# TSOC_GROVEY_WIFI_R0_1.net
KiCad netlist of a schematic drawn in EAGLE
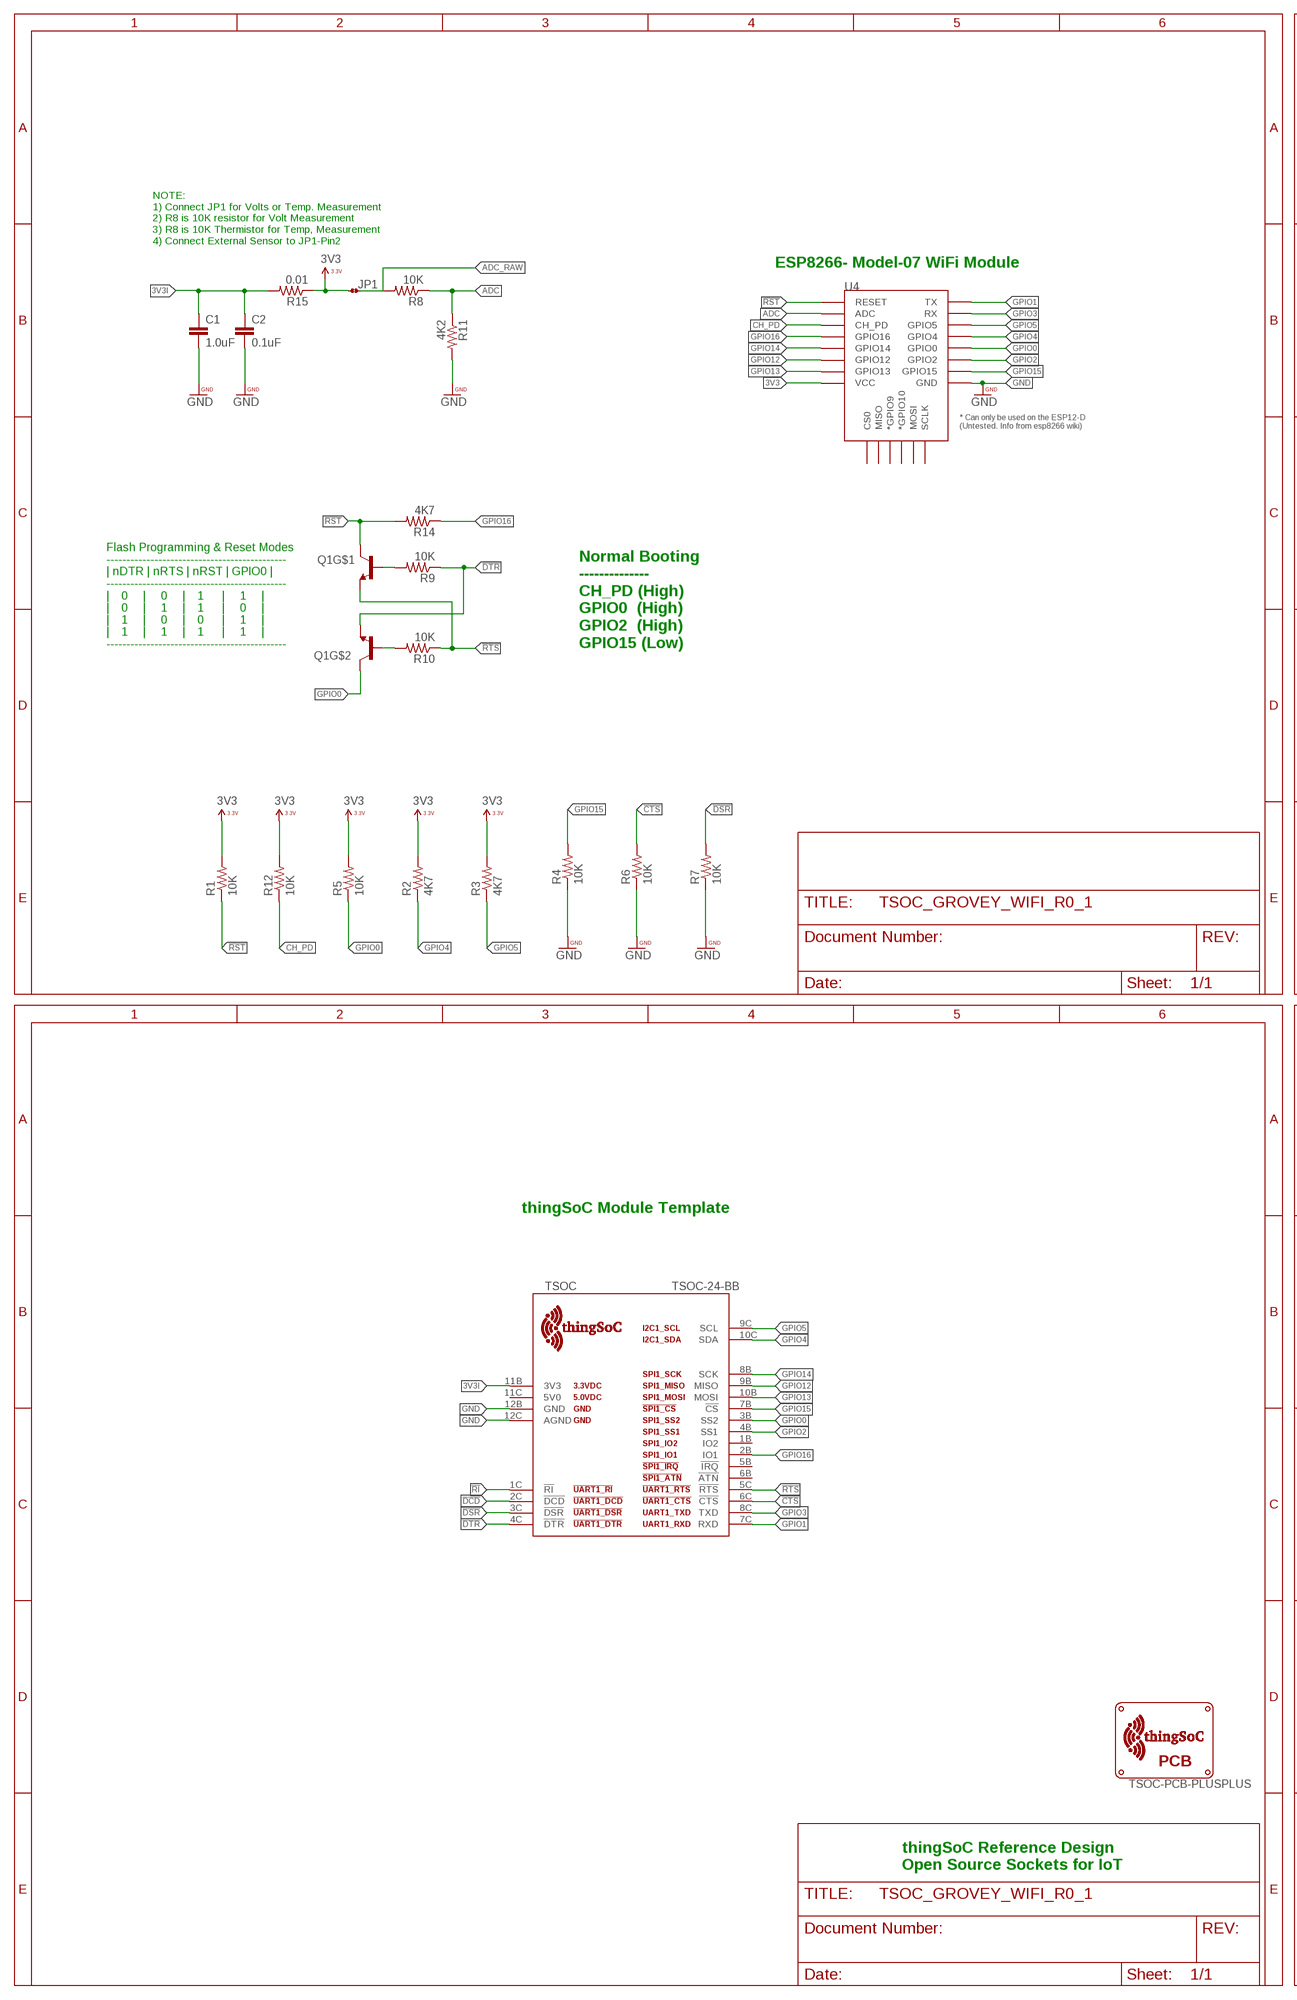
[diagram p0: schematic, sheet 1, part 1 of 2]
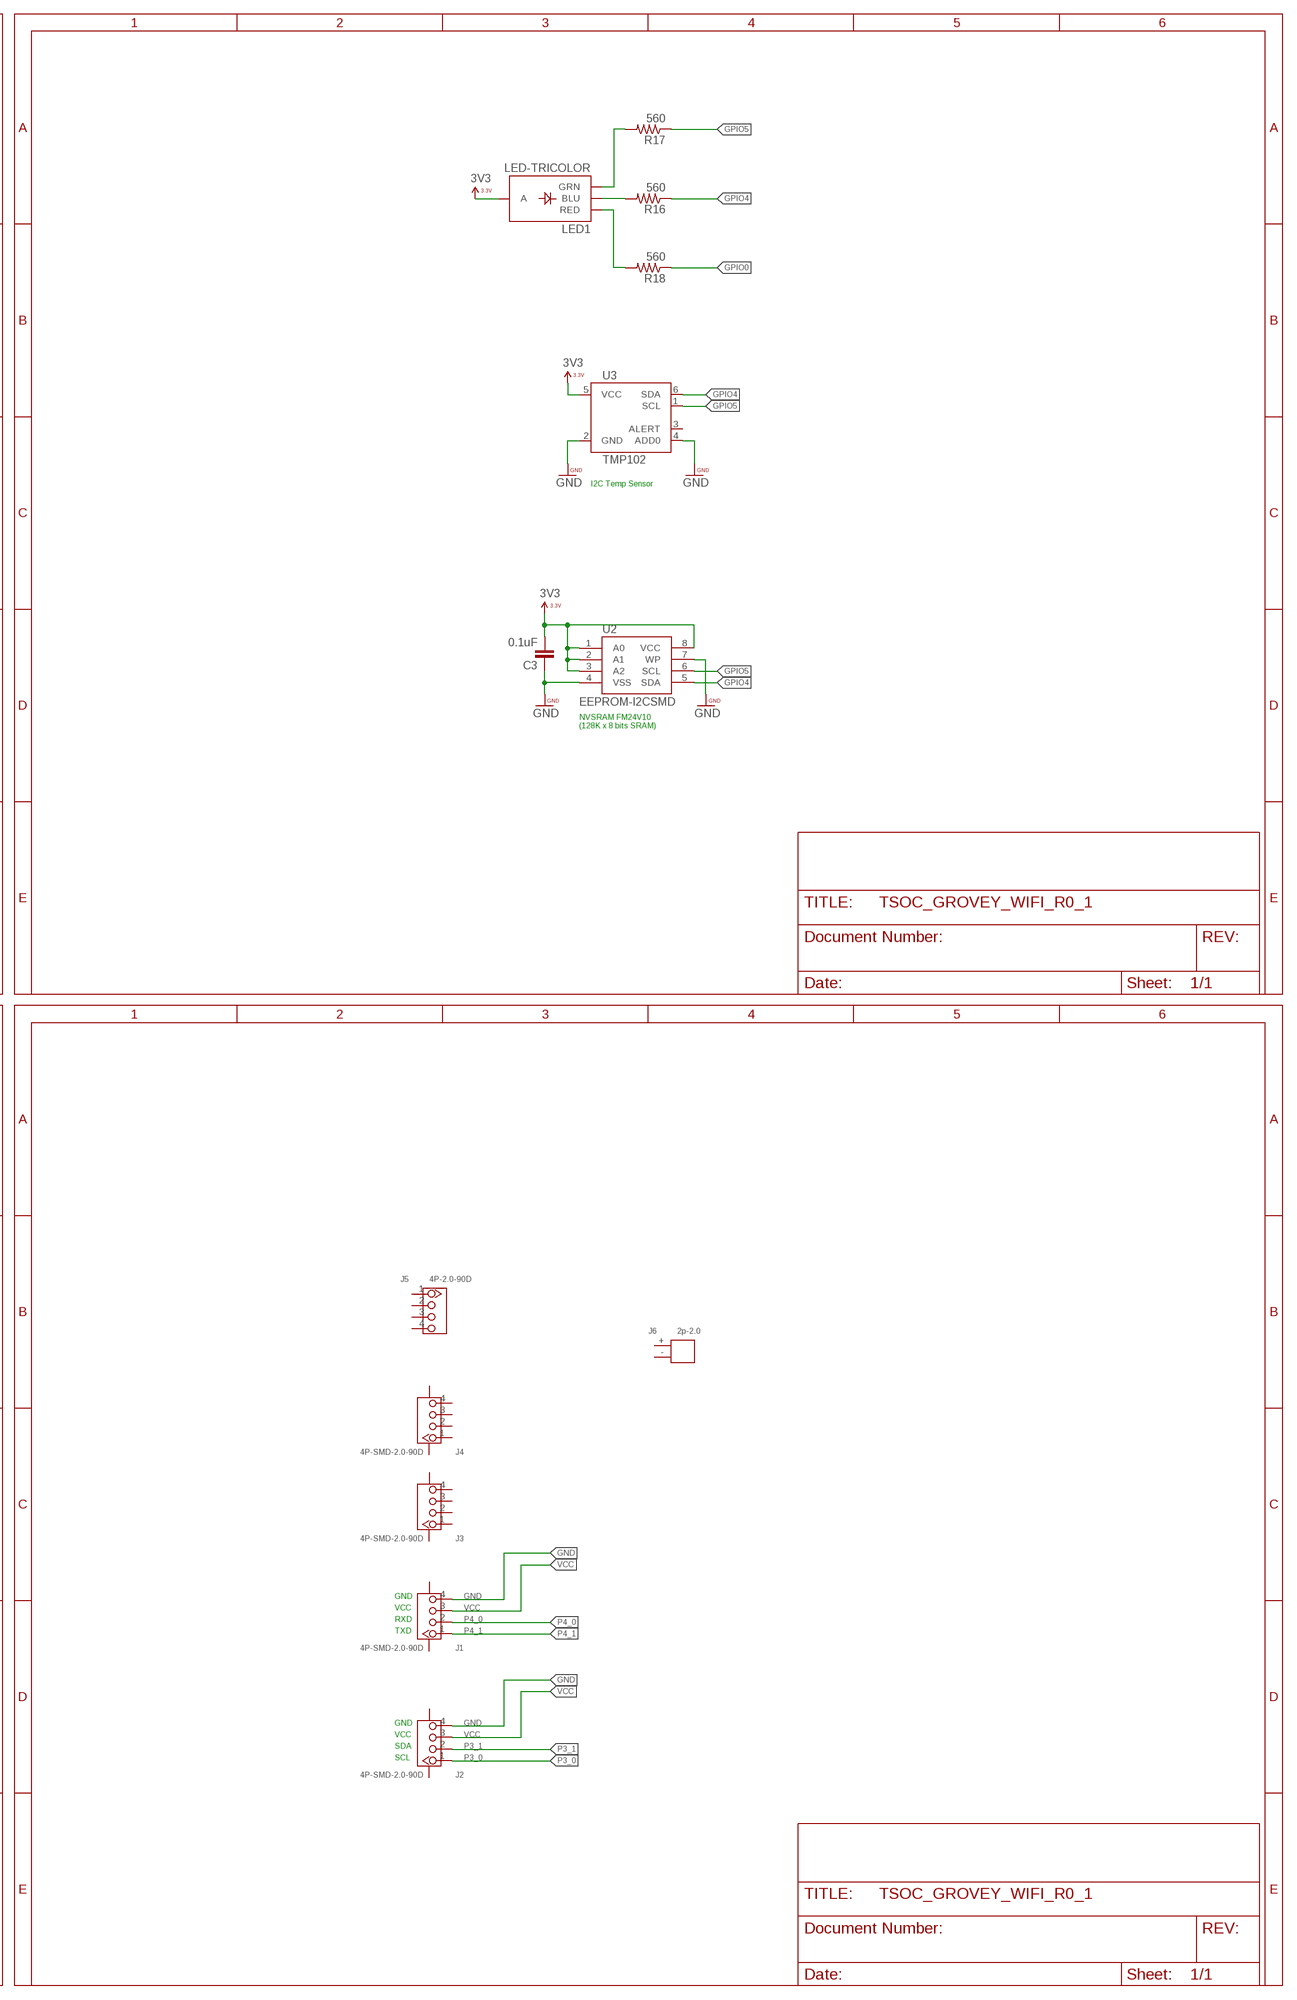
[diagram p1: schematic, sheet 1, part 2 of 2]

(export (version "E")
  (design (tool "Eeschema 10.0.6"))
  (components
    (comp (ref "C1")
      (value "1.0uF")
      (footprint "eagle-import:0402-CAP")
      (libsource (lib "eagle-import") (part "CAP0402-CAP"))
    )
    (comp (ref "C2")
      (value "0.1uF")
      (footprint "eagle-import:0402-CAP")
      (libsource (lib "eagle-import") (part "CAP0402-CAP"))
    )
    (comp (ref "C3")
      (value "0.1uF")
      (footprint "eagle-import:0402-CAP")
      (libsource (lib "eagle-import") (part "CAP0402-CAP"))
    )
    (comp (ref "J1")
      (value "4P-SMD-2.0-90D")
      (footprint "eagle-import:HW4-SMD-2.0-90D")
      (libsource (lib "eagle-import") (part "GROVE-CONNECTOR-SMD-90D(4+2P-2.0)"))
    )
    (comp (ref "J2")
      (value "4P-SMD-2.0-90D")
      (footprint "eagle-import:HW4-SMD-2.0-90D")
      (libsource (lib "eagle-import") (part "GROVE-CONNECTOR-SMD-90D(4+2P-2.0)"))
    )
    (comp (ref "J3")
      (value "4P-SMD-2.0-90D")
      (footprint "eagle-import:HW4-SMD-2.0-90D")
      (libsource (lib "eagle-import") (part "GROVE-CONNECTOR-SMD-90D(4+2P-2.0)"))
    )
    (comp (ref "J4")
      (value "4P-SMD-2.0-90D")
      (footprint "eagle-import:HW4-SMD-2.0-90D")
      (libsource (lib "eagle-import") (part "GROVE-CONNECTOR-SMD-90D(4+2P-2.0)"))
    )
    (comp (ref "J5")
      (value "4P-2.0-90D")
      (footprint "eagle-import:HW4-2.0-90D")
      (libsource (lib "eagle-import") (part "GROVE-CONNECTOR-DIP-90D(4P-2.0)"))
    )
    (comp (ref "J6")
      (value "2p-2.0")
      (footprint "eagle-import:H2-2.0-6X4.5MM")
      (libsource (lib "eagle-import") (part "DIP-JST-2P-2.0"))
    )
    (comp (ref "JP1")
      (value "JMP-2-NO-0402")
      (footprint "eagle-import:JMP-2-NO-0402")
      (libsource (lib "eagle-import") (part "JMP-2-NO-0402"))
    )
    (comp (ref "LED1")
      (value "LED-TRICOLOR")
      (footprint "eagle-import:LED-TRICOLOR-SMD")
      (libsource (lib "eagle-import") (part "LED-TRICOLOR"))
    )
    (comp (ref "Q1")
      (value "MMBT2222A")
      (footprint "eagle-import:SOT363")
      (libsource (lib "eagle-import") (part "MMDT3904"))
    )
    (comp (ref "R1")
      (value "10K")
      (footprint "eagle-import:0402-RES")
      (libsource (lib "eagle-import") (part "RESISTOR0402"))
    )
    (comp (ref "R2")
      (value "4K7")
      (footprint "eagle-import:0402-RES")
      (libsource (lib "eagle-import") (part "RESISTOR0402"))
    )
    (comp (ref "R3")
      (value "4K7")
      (footprint "eagle-import:0402-RES")
      (libsource (lib "eagle-import") (part "RESISTOR0402"))
    )
    (comp (ref "R4")
      (value "10K")
      (footprint "eagle-import:0402-RES")
      (libsource (lib "eagle-import") (part "RESISTOR0402"))
    )
    (comp (ref "R5")
      (value "10K")
      (footprint "eagle-import:0402-RES")
      (libsource (lib "eagle-import") (part "RESISTOR0402"))
    )
    (comp (ref "R6")
      (value "10K")
      (footprint "eagle-import:0402-RES")
      (libsource (lib "eagle-import") (part "RESISTOR0402"))
    )
    (comp (ref "R7")
      (value "10K")
      (footprint "eagle-import:0402-RES")
      (libsource (lib "eagle-import") (part "RESISTOR0402"))
    )
    (comp (ref "R8")
      (value "10K")
      (footprint "eagle-import:0402-RES")
      (libsource (lib "eagle-import") (part "RESISTOR0402"))
    )
    (comp (ref "R9")
      (value "10K")
      (footprint "eagle-import:0402-RES")
      (libsource (lib "eagle-import") (part "RESISTOR0402"))
    )
    (comp (ref "R10")
      (value "10K")
      (footprint "eagle-import:0402-RES")
      (libsource (lib "eagle-import") (part "RESISTOR0402"))
    )
    (comp (ref "R11")
      (value "4K2")
      (footprint "eagle-import:0402-RES")
      (libsource (lib "eagle-import") (part "RESISTOR0402"))
    )
    (comp (ref "R12")
      (value "10K")
      (footprint "eagle-import:0402-RES")
      (libsource (lib "eagle-import") (part "RESISTOR0402"))
    )
    (comp (ref "R14")
      (value "4K7")
      (footprint "eagle-import:0402-RES")
      (libsource (lib "eagle-import") (part "RESISTOR0402"))
    )
    (comp (ref "R15")
      (value "0.01")
      (footprint "eagle-import:0402-RES")
      (libsource (lib "eagle-import") (part "RESISTOR0402"))
    )
    (comp (ref "R16")
      (value "560")
      (footprint "eagle-import:0402-RES")
      (libsource (lib "eagle-import") (part "RESISTOR0402"))
    )
    (comp (ref "R17")
      (value "560")
      (footprint "eagle-import:0402-RES")
      (libsource (lib "eagle-import") (part "RESISTOR0402"))
    )
    (comp (ref "R18")
      (value "560")
      (footprint "eagle-import:0402-RES")
      (libsource (lib "eagle-import") (part "RESISTOR0402"))
    )
    (comp (ref "TSOC")
      (value "TSOC-24-BB")
      (footprint "eagle-import:TSOC-BB-S24")
      (libsource (lib "eagle-import") (part "TSOC-24-BB"))
    )
    (comp (ref "U$11")
      (value "TSOC-PCB-PLUSPLUS")
      (footprint "eagle-import:TSOC-BB-BRD-PLUS-PLUS-DIM")
      (libsource (lib "eagle-import") (part "TSOC-PCB-PLUSPLUS"))
    )
    (comp (ref "U2")
      (value "EEPROM-I2CSMD")
      (footprint "eagle-import:SO08")
      (libsource (lib "eagle-import") (part "EEPROM-I2CSMD"))
    )
    (comp (ref "U3")
      (value "TMP102")
      (footprint "eagle-import:SOT563")
      (libsource (lib "eagle-import") (part "TMP102"))
    )
    (comp (ref "U4")
      (value "ESP12ESMD")
      (footprint "eagle-import:ESP12E-SMD")
      (libsource (lib "eagle-import") (part "ESP12ESMD"))
    )
  )
  (nets
    (net (code "1") (name "/~{CTS}") (class "Default")
      (node (ref "R6") (pin "2") (pinfunction "2_2") (pintype "passive"))
      (node (ref "TSOC") (pin "6C") (pinfunction "~{CTS}_6C") (pintype "bidirectional"))
    )
    (net (code "2") (name "/~{DCD}") (class "Default")
      (node (ref "TSOC") (pin "2C") (pinfunction "~{DCD}_2C") (pintype "bidirectional"))
    )
    (net (code "3") (name "/~{DSR}") (class "Default")
      (node (ref "R7") (pin "2") (pinfunction "2_2") (pintype "passive"))
      (node (ref "TSOC") (pin "3C") (pinfunction "~{DSR}_3C") (pintype "bidirectional"))
    )
    (net (code "4") (name "/~{DTR}") (class "Default")
      (node (ref "Q1") (pin "1") (pinfunction "E_1") (pintype "passive"))
      (node (ref "R9") (pin "1") (pinfunction "1_1") (pintype "passive"))
      (node (ref "TSOC") (pin "4C") (pinfunction "~{DTR}_4C") (pintype "bidirectional"))
    )
    (net (code "5") (name "/~{RI}") (class "Default")
      (node (ref "TSOC") (pin "1C") (pinfunction "~{RI}_1C") (pintype "bidirectional"))
    )
    (net (code "6") (name "/~{RST}") (class "Default")
      (node (ref "Q1") (pin "3") (pinfunction "C_3") (pintype "passive"))
      (node (ref "R1") (pin "1") (pinfunction "1_1") (pintype "passive"))
      (node (ref "R14") (pin "2") (pinfunction "2_2") (pintype "passive"))
      (node (ref "U4") (pin "RESET") (pinfunction "RESET_RESET") (pintype "bidirectional"))
    )
    (net (code "7") (name "/~{RTS}") (class "Default")
      (node (ref "Q1") (pin "4") (pinfunction "E_4") (pintype "passive"))
      (node (ref "R10") (pin "1") (pinfunction "1_1") (pintype "passive"))
      (node (ref "TSOC") (pin "5C") (pinfunction "~{RTS}_5C") (pintype "bidirectional"))
    )
    (net (code "8") (name "3V3") (class "Default")
      (node (ref "C3") (pin "2") (pinfunction "2_2") (pintype "passive"))
      (node (ref "JP1") (pin "1") (pinfunction "1_1") (pintype "passive"))
      (node (ref "LED1") (pin "A") (pinfunction "A_A") (pintype "bidirectional"))
      (node (ref "R1") (pin "2") (pinfunction "2_2") (pintype "passive"))
      (node (ref "R12") (pin "2") (pinfunction "2_2") (pintype "passive"))
      (node (ref "R15") (pin "1") (pinfunction "1_1") (pintype "passive"))
      (node (ref "R2") (pin "2") (pinfunction "2_2") (pintype "passive"))
      (node (ref "R3") (pin "2") (pinfunction "2_2") (pintype "passive"))
      (node (ref "R5") (pin "2") (pinfunction "2_2") (pintype "passive"))
      (node (ref "U2") (pin "1") (pinfunction "A0_1") (pintype "bidirectional"))
      (node (ref "U2") (pin "2") (pinfunction "A1_2") (pintype "bidirectional"))
      (node (ref "U2") (pin "3") (pinfunction "A2_3") (pintype "bidirectional"))
      (node (ref "U2") (pin "8") (pinfunction "VCC_8") (pintype "power_in"))
      (node (ref "U3") (pin "5") (pinfunction "VCC_5") (pintype "bidirectional"))
      (node (ref "U4") (pin "VCC") (pinfunction "VCC_VCC") (pintype "bidirectional"))
    )
    (net (code "9") (name "3V3I") (class "Default")
      (node (ref "C1") (pin "1") (pinfunction "1_1") (pintype "passive"))
      (node (ref "C2") (pin "1") (pinfunction "1_1") (pintype "passive"))
      (node (ref "R15") (pin "2") (pinfunction "2_2") (pintype "passive"))
      (node (ref "TSOC") (pin "11B") (pinfunction "3V3_11B") (pintype "bidirectional"))
    )
    (net (code "10") (name "ADC") (class "Default")
      (node (ref "R11") (pin "1") (pinfunction "1_1") (pintype "passive"))
      (node (ref "R8") (pin "1") (pinfunction "1_1") (pintype "passive"))
      (node (ref "U4") (pin "ADC") (pinfunction "ADC_ADC") (pintype "bidirectional"))
    )
    (net (code "11") (name "ADC_RAW") (class "Default")
      (node (ref "JP1") (pin "2") (pinfunction "2_2") (pintype "passive"))
      (node (ref "R8") (pin "2") (pinfunction "2_2") (pintype "passive"))
    )
    (net (code "12") (name "CH_PD") (class "Default")
      (node (ref "R12") (pin "1") (pinfunction "1_1") (pintype "passive"))
      (node (ref "U4") (pin "CH_PD") (pinfunction "CH_PD_CH_PD") (pintype "bidirectional"))
    )
    (net (code "13") (name "GND") (class "Default")
      (node (ref "C1") (pin "2") (pinfunction "2_2") (pintype "passive"))
      (node (ref "C2") (pin "2") (pinfunction "2_2") (pintype "passive"))
      (node (ref "C3") (pin "1") (pinfunction "1_1") (pintype "passive"))
      (node (ref "J1") (pin "4") (pinfunction "4_4") (pintype "bidirectional"))
      (node (ref "J2") (pin "4") (pinfunction "4_4") (pintype "bidirectional"))
      (node (ref "R11") (pin "2") (pinfunction "2_2") (pintype "passive"))
      (node (ref "R4") (pin "1") (pinfunction "1_1") (pintype "passive"))
      (node (ref "R6") (pin "1") (pinfunction "1_1") (pintype "passive"))
      (node (ref "R7") (pin "1") (pinfunction "1_1") (pintype "passive"))
      (node (ref "TSOC") (pin "12B") (pinfunction "GND_12B") (pintype "bidirectional"))
      (node (ref "TSOC") (pin "12C") (pinfunction "AGND_12C") (pintype "bidirectional"))
      (node (ref "U2") (pin "4") (pinfunction "VSS_4") (pintype "power_in"))
      (node (ref "U2") (pin "7") (pinfunction "WP_7") (pintype "bidirectional"))
      (node (ref "U3") (pin "2") (pinfunction "GND_2") (pintype "bidirectional"))
      (node (ref "U3") (pin "4") (pinfunction "ADD0_4") (pintype "bidirectional"))
      (node (ref "U4") (pin "GND") (pinfunction "GND_GND") (pintype "bidirectional"))
    )
    (net (code "14") (name "GPIO0") (class "Default")
      (node (ref "Q1") (pin "6") (pinfunction "C_6") (pintype "passive"))
      (node (ref "R18") (pin "1") (pinfunction "1_1") (pintype "passive"))
      (node (ref "R5") (pin "1") (pinfunction "1_1") (pintype "passive"))
      (node (ref "TSOC") (pin "3B") (pinfunction "SS2_3B") (pintype "bidirectional"))
      (node (ref "U4") (pin "GPIO0") (pinfunction "GPIO0_GPIO0") (pintype "bidirectional"))
    )
    (net (code "15") (name "GPIO1") (class "Default")
      (node (ref "TSOC") (pin "7C") (pinfunction "RXD_7C") (pintype "bidirectional"))
      (node (ref "U4") (pin "TXD0") (pinfunction "TX_TXD0") (pintype "bidirectional"))
    )
    (net (code "16") (name "GPIO2") (class "Default")
      (node (ref "TSOC") (pin "4B") (pinfunction "SS1_4B") (pintype "bidirectional"))
      (node (ref "U4") (pin "GPIO2") (pinfunction "GPIO2_GPIO2") (pintype "bidirectional"))
    )
    (net (code "17") (name "GPIO3") (class "Default")
      (node (ref "TSOC") (pin "8C") (pinfunction "TXD_8C") (pintype "bidirectional"))
      (node (ref "U4") (pin "RXD0") (pinfunction "RX_RXD0") (pintype "bidirectional"))
    )
    (net (code "18") (name "GPIO4") (class "Default")
      (node (ref "R16") (pin "1") (pinfunction "1_1") (pintype "passive"))
      (node (ref "R2") (pin "1") (pinfunction "1_1") (pintype "passive"))
      (node (ref "TSOC") (pin "10C") (pinfunction "SDA_10C") (pintype "bidirectional"))
      (node (ref "U2") (pin "5") (pinfunction "SDA_5") (pintype "bidirectional"))
      (node (ref "U3") (pin "6") (pinfunction "SDA_6") (pintype "bidirectional"))
      (node (ref "U4") (pin "GPIO4") (pinfunction "GPIO4_GPIO4") (pintype "bidirectional"))
    )
    (net (code "19") (name "GPIO5") (class "Default")
      (node (ref "R17") (pin "1") (pinfunction "1_1") (pintype "passive"))
      (node (ref "R3") (pin "1") (pinfunction "1_1") (pintype "passive"))
      (node (ref "TSOC") (pin "9C") (pinfunction "SCL_9C") (pintype "bidirectional"))
      (node (ref "U2") (pin "6") (pinfunction "SCL_6") (pintype "bidirectional"))
      (node (ref "U3") (pin "1") (pinfunction "SCL_1") (pintype "bidirectional"))
      (node (ref "U4") (pin "GPIO5") (pinfunction "GPIO5_GPIO5") (pintype "bidirectional"))
    )
    (net (code "20") (name "GPIO12") (class "Default")
      (node (ref "TSOC") (pin "9B") (pinfunction "MISO_9B") (pintype "bidirectional"))
      (node (ref "U4") (pin "GPIO12") (pinfunction "GPIO12_GPIO12") (pintype "bidirectional"))
    )
    (net (code "21") (name "GPIO13") (class "Default")
      (node (ref "TSOC") (pin "10B") (pinfunction "MOSI_10B") (pintype "bidirectional"))
      (node (ref "U4") (pin "GPIO13") (pinfunction "GPIO13_GPIO13") (pintype "bidirectional"))
    )
    (net (code "22") (name "GPIO14") (class "Default")
      (node (ref "TSOC") (pin "8B") (pinfunction "SCK_8B") (pintype "bidirectional"))
      (node (ref "U4") (pin "GPIO14") (pinfunction "GPIO14_GPIO14") (pintype "bidirectional"))
    )
    (net (code "23") (name "GPIO15") (class "Default")
      (node (ref "R4") (pin "2") (pinfunction "2_2") (pintype "passive"))
      (node (ref "TSOC") (pin "7B") (pinfunction "~{CS}_7B") (pintype "bidirectional"))
      (node (ref "U4") (pin "GPIO15") (pinfunction "GPIO15_GPIO15") (pintype "bidirectional"))
    )
    (net (code "24") (name "GPIO16") (class "Default")
      (node (ref "R14") (pin "1") (pinfunction "1_1") (pintype "passive"))
      (node (ref "TSOC") (pin "2B") (pinfunction "IO1_2B") (pintype "bidirectional"))
      (node (ref "U4") (pin "GPIO16") (pinfunction "GPIO16_GPIO16") (pintype "bidirectional"))
    )
    (net (code "25") (name "Net-(LED1-BLU)") (class "Default")
      (node (ref "LED1") (pin "B") (pinfunction "BLU_B") (pintype "bidirectional"))
      (node (ref "R16") (pin "2") (pinfunction "2_2") (pintype "passive"))
    )
    (net (code "26") (name "Net-(LED1-GRN)") (class "Default")
      (node (ref "LED1") (pin "G") (pinfunction "GRN_G") (pintype "bidirectional"))
      (node (ref "R17") (pin "2") (pinfunction "2_2") (pintype "passive"))
    )
    (net (code "27") (name "Net-(LED1-RED)") (class "Default")
      (node (ref "LED1") (pin "R") (pinfunction "RED_R") (pintype "bidirectional"))
      (node (ref "R18") (pin "2") (pinfunction "2_2") (pintype "passive"))
    )
    (net (code "28") (name "Net-(Q1A-B)") (class "Default")
      (node (ref "Q1") (pin "5") (pinfunction "B_5") (pintype "passive"))
      (node (ref "R9") (pin "2") (pinfunction "2_2") (pintype "passive"))
    )
    (net (code "29") (name "Net-(Q1B-B)") (class "Default")
      (node (ref "Q1") (pin "2") (pinfunction "B_2") (pintype "passive"))
      (node (ref "R10") (pin "2") (pinfunction "2_2") (pintype "passive"))
    )
    (net (code "30") (name "P3_0") (class "Default")
      (node (ref "J2") (pin "1") (pinfunction "1_1") (pintype "bidirectional"))
    )
    (net (code "31") (name "P3_1") (class "Default")
      (node (ref "J2") (pin "2") (pinfunction "2_2") (pintype "bidirectional"))
    )
    (net (code "32") (name "P4_0") (class "Default")
      (node (ref "J1") (pin "2") (pinfunction "2_2") (pintype "bidirectional"))
    )
    (net (code "33") (name "P4_1") (class "Default")
      (node (ref "J1") (pin "1") (pinfunction "1_1") (pintype "bidirectional"))
    )
    (net (code "34") (name "VCC") (class "Default")
      (node (ref "J1") (pin "3") (pinfunction "3_3") (pintype "bidirectional"))
      (node (ref "J2") (pin "3") (pinfunction "3_3") (pintype "bidirectional"))
    )
    (net (code "35") (name "unconnected-(J1-PadSS1)") (class "Default")
      (node (ref "J1") (pin "SS1") (pinfunction "SS1_SS1") (pintype "bidirectional"))
    )
    (net (code "36") (name "unconnected-(J1-PadSS2)") (class "Default")
      (node (ref "J1") (pin "SS2") (pinfunction "SS2_SS2") (pintype "bidirectional"))
    )
    (net (code "37") (name "unconnected-(J2-PadSS1)") (class "Default")
      (node (ref "J2") (pin "SS1") (pinfunction "SS1_SS1") (pintype "bidirectional"))
    )
    (net (code "38") (name "unconnected-(J2-PadSS2)") (class "Default")
      (node (ref "J2") (pin "SS2") (pinfunction "SS2_SS2") (pintype "bidirectional"))
    )
    (net (code "39") (name "unconnected-(J3-Pad1)") (class "Default")
      (node (ref "J3") (pin "1") (pinfunction "1_1") (pintype "bidirectional"))
    )
    (net (code "40") (name "unconnected-(J3-Pad2)") (class "Default")
      (node (ref "J3") (pin "2") (pinfunction "2_2") (pintype "bidirectional"))
    )
    (net (code "41") (name "unconnected-(J3-Pad3)") (class "Default")
      (node (ref "J3") (pin "3") (pinfunction "3_3") (pintype "bidirectional"))
    )
    (net (code "42") (name "unconnected-(J3-Pad4)") (class "Default")
      (node (ref "J3") (pin "4") (pinfunction "4_4") (pintype "bidirectional"))
    )
    (net (code "43") (name "unconnected-(J3-PadSS1)") (class "Default")
      (node (ref "J3") (pin "SS1") (pinfunction "SS1_SS1") (pintype "bidirectional"))
    )
    (net (code "44") (name "unconnected-(J3-PadSS2)") (class "Default")
      (node (ref "J3") (pin "SS2") (pinfunction "SS2_SS2") (pintype "bidirectional"))
    )
    (net (code "45") (name "unconnected-(J4-Pad1)") (class "Default")
      (node (ref "J4") (pin "1") (pinfunction "1_1") (pintype "bidirectional"))
    )
    (net (code "46") (name "unconnected-(J4-Pad2)") (class "Default")
      (node (ref "J4") (pin "2") (pinfunction "2_2") (pintype "bidirectional"))
    )
    (net (code "47") (name "unconnected-(J4-Pad3)") (class "Default")
      (node (ref "J4") (pin "3") (pinfunction "3_3") (pintype "bidirectional"))
    )
    (net (code "48") (name "unconnected-(J4-Pad4)") (class "Default")
      (node (ref "J4") (pin "4") (pinfunction "4_4") (pintype "bidirectional"))
    )
    (net (code "49") (name "unconnected-(J4-PadSS1)") (class "Default")
      (node (ref "J4") (pin "SS1") (pinfunction "SS1_SS1") (pintype "bidirectional"))
    )
    (net (code "50") (name "unconnected-(J4-PadSS2)") (class "Default")
      (node (ref "J4") (pin "SS2") (pinfunction "SS2_SS2") (pintype "bidirectional"))
    )
    (net (code "51") (name "unconnected-(J5-Pad1)") (class "Default")
      (node (ref "J5") (pin "1") (pinfunction "1_1") (pintype "bidirectional"))
    )
    (net (code "52") (name "unconnected-(J5-Pad2)") (class "Default")
      (node (ref "J5") (pin "2") (pinfunction "2_2") (pintype "bidirectional"))
    )
    (net (code "53") (name "unconnected-(J5-Pad3)") (class "Default")
      (node (ref "J5") (pin "3") (pinfunction "3_3") (pintype "bidirectional"))
    )
    (net (code "54") (name "unconnected-(J5-Pad4)") (class "Default")
      (node (ref "J5") (pin "4") (pinfunction "4_4") (pintype "bidirectional"))
    )
    (net (code "55") (name "unconnected-(J6-P$1-Pad+)") (class "Default")
      (node (ref "J6") (pin "+") (pinfunction "P$1_+") (pintype "bidirectional"))
    )
    (net (code "56") (name "unconnected-(J6-P$2-Pad-)") (class "Default")
      (node (ref "J6") (pin "-") (pinfunction "P$2_-") (pintype "bidirectional"))
    )
    (net (code "57") (name "unconnected-(TSOC-5V0-Pad11C)") (class "Default")
      (node (ref "TSOC") (pin "11C") (pinfunction "5V0_11C") (pintype "bidirectional"))
    )
    (net (code "58") (name "unconnected-(TSOC-IO2-Pad1B)") (class "Default")
      (node (ref "TSOC") (pin "1B") (pinfunction "IO2_1B") (pintype "bidirectional"))
    )
    (net (code "59") (name "unconnected-(TSOC-~{ATN}-Pad6B)") (class "Default")
      (node (ref "TSOC") (pin "6B") (pinfunction "~{ATN}_6B") (pintype "bidirectional"))
    )
    (net (code "60") (name "unconnected-(TSOC-~{IRQ}-Pad5B)") (class "Default")
      (node (ref "TSOC") (pin "5B") (pinfunction "~{IRQ}_5B") (pintype "bidirectional"))
    )
    (net (code "61") (name "unconnected-(U3-ALERT-Pad3)") (class "Default")
      (node (ref "U3") (pin "3") (pinfunction "ALERT_3") (pintype "bidirectional"))
    )
    (net (code "62") (name "unconnected-(U4-*GPIO9-PadGPIO9)") (class "Default")
      (node (ref "U4") (pin "GPIO9") (pinfunction "*GPIO9_GPIO9") (pintype "bidirectional"))
    )
    (net (code "63") (name "unconnected-(U4-*GPIO10-PadGPIO10)") (class "Default")
      (node (ref "U4") (pin "GPIO10") (pinfunction "*GPIO10_GPIO10") (pintype "bidirectional"))
    )
    (net (code "64") (name "unconnected-(U4-PadCS0)") (class "Default")
      (node (ref "U4") (pin "CS0") (pinfunction "CS0_CS0") (pintype "bidirectional"))
    )
    (net (code "65") (name "unconnected-(U4-PadMISO)") (class "Default")
      (node (ref "U4") (pin "MISO") (pinfunction "MISO_MISO") (pintype "bidirectional"))
    )
    (net (code "66") (name "unconnected-(U4-PadMOSI)") (class "Default")
      (node (ref "U4") (pin "MOSI") (pinfunction "MOSI_MOSI") (pintype "bidirectional"))
    )
    (net (code "67") (name "unconnected-(U4-PadSCLK)") (class "Default")
      (node (ref "U4") (pin "SCLK") (pinfunction "SCLK_SCLK") (pintype "bidirectional"))
    )
  )
)
